# placa_mux.net
KiCad netlist of a schematic drawn in EAGLE
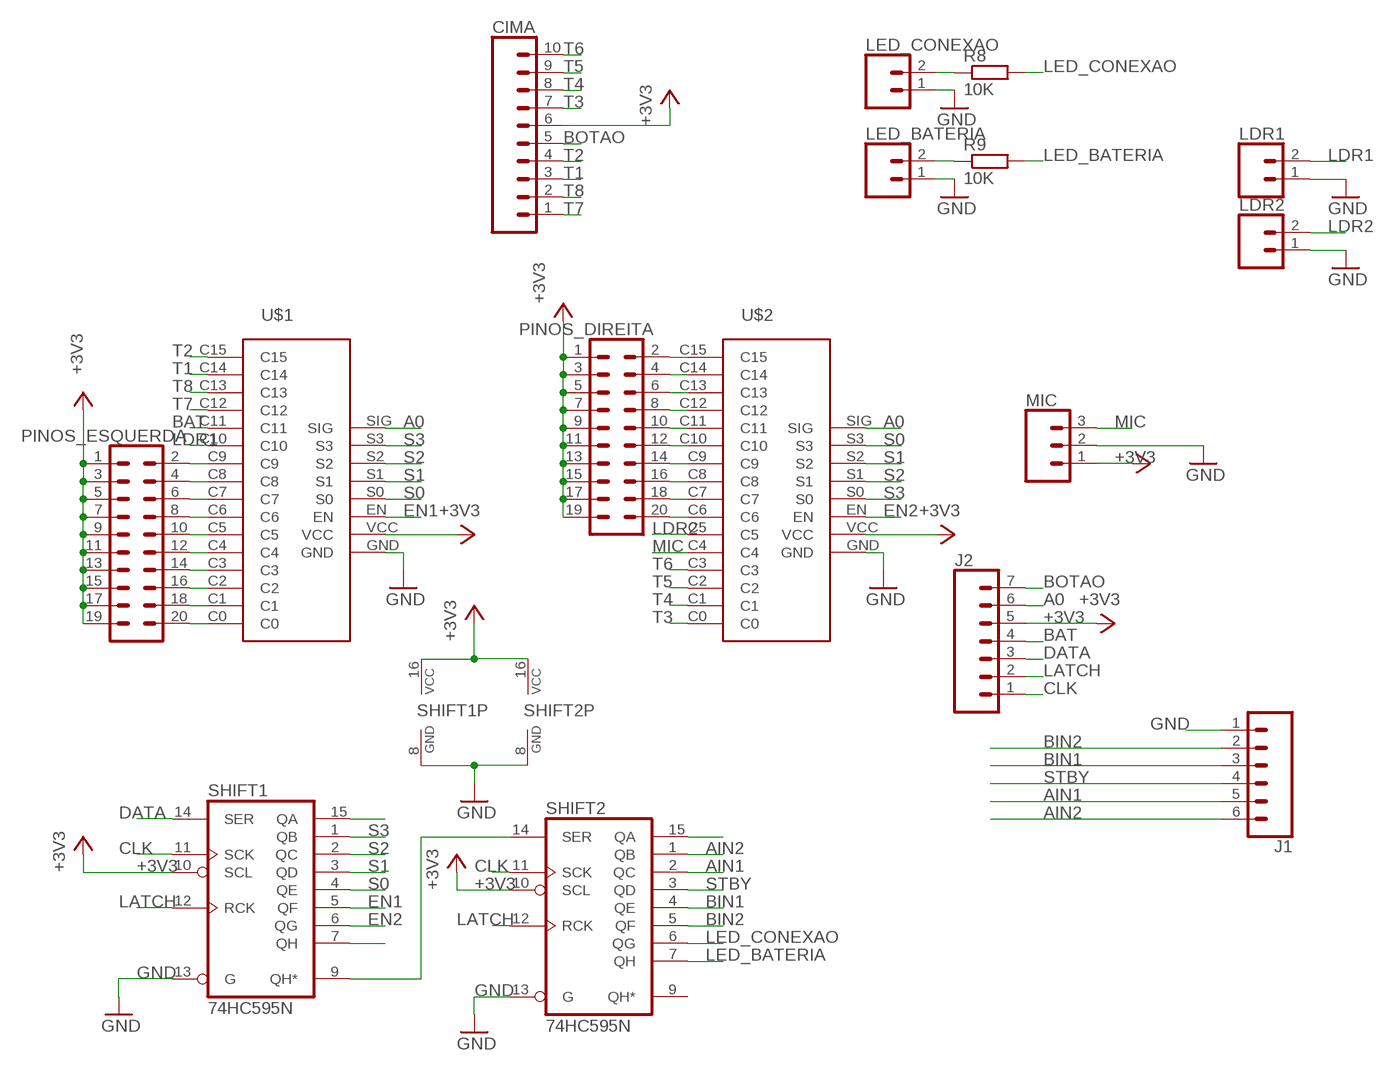
[diagram p0: schematic, sheet 1]

(export (version "E")
  (design (tool "Eeschema 10.0.6"))
  (components
    (comp (ref "CIMA")
      (value "CONN_10\"")
      (footprint "eagle-import:1X10")
      (libsource (lib "eagle-import") (part "CONN_10{dblquote}"))
    )
    (comp (ref "J1")
      (value "CONN_06SILK_FEMALE_PTH")
      (footprint "eagle-import:1X06")
      (libsource (lib "eagle-import") (part "CONN_06SILK_FEMALE_PTH"))
    )
    (comp (ref "J2")
      (value "CONN_07")
      (footprint "eagle-import:1X07")
      (libsource (lib "eagle-import") (part "CONN_07"))
    )
    (comp (ref "LDR1")
      (value "CONN_02")
      (footprint "eagle-import:1X02")
      (libsource (lib "eagle-import") (part "CONN_02"))
    )
    (comp (ref "LDR2")
      (value "CONN_02")
      (footprint "eagle-import:1X02")
      (libsource (lib "eagle-import") (part "CONN_02"))
    )
    (comp (ref "LED_BATERIA")
      (value "CONN_02")
      (footprint "eagle-import:1X02")
      (libsource (lib "eagle-import") (part "CONN_02"))
    )
    (comp (ref "LED_CONEXAO")
      (value "CONN_02")
      (footprint "eagle-import:1X02")
      (libsource (lib "eagle-import") (part "CONN_02"))
    )
    (comp (ref "MIC")
      (value "CONN_03")
      (footprint "eagle-import:1X03")
      (libsource (lib "eagle-import") (part "CONN_03"))
    )
    (comp (ref "PINOS_DIREITA")
      (value "CONN_10X2")
      (footprint "eagle-import:2X10")
      (libsource (lib "eagle-import") (part "CONN_10X2"))
    )
    (comp (ref "PINOS_ESQUERDA")
      (value "CONN_10X2")
      (footprint "eagle-import:2X10")
      (libsource (lib "eagle-import") (part "CONN_10X2"))
    )
    (comp (ref "R8")
      (value "10K")
      (footprint "eagle-import:0204_7")
      (libsource (lib "eagle-import") (part "R-EU_0204/7"))
    )
    (comp (ref "R9")
      (value "10K")
      (footprint "eagle-import:0204_7")
      (libsource (lib "eagle-import") (part "R-EU_0204/7"))
    )
    (comp (ref "SHIFT1")
      (value "74HC595N")
      (footprint "eagle-import:DIL16")
      (libsource (lib "eagle-import") (part "74595NHC"))
    )
    (comp (ref "SHIFT2")
      (value "74HC595N")
      (footprint "eagle-import:DIL16")
      (libsource (lib "eagle-import") (part "74595NHC"))
    )
    (comp (ref "U$1")
      (value "4067_MODULE")
      (footprint "eagle-import:4067_MODULE")
      (libsource (lib "eagle-import") (part "4067_MODULE"))
    )
    (comp (ref "U$2")
      (value "4067_MODULE")
      (footprint "eagle-import:4067_MODULE")
      (libsource (lib "eagle-import") (part "4067_MODULE"))
    )
  )
  (nets
    (net (code "1") (name "+3V3") (class "Default")
      (node (ref "CIMA") (pin "6") (pinfunction "6_6") (pintype "passive"))
      (node (ref "J2") (pin "5") (pinfunction "5_5") (pintype "passive"))
      (node (ref "MIC") (pin "1") (pinfunction "1_1") (pintype "passive"))
      (node (ref "PINOS_DIREITA") (pin "1") (pinfunction "1_1") (pintype "passive"))
      (node (ref "PINOS_DIREITA") (pin "11") (pinfunction "11_11") (pintype "passive"))
      (node (ref "PINOS_DIREITA") (pin "13") (pinfunction "13_13") (pintype "passive"))
      (node (ref "PINOS_DIREITA") (pin "15") (pinfunction "15_15") (pintype "passive"))
      (node (ref "PINOS_DIREITA") (pin "17") (pinfunction "17_17") (pintype "passive"))
      (node (ref "PINOS_DIREITA") (pin "19") (pinfunction "19_19") (pintype "passive"))
      (node (ref "PINOS_DIREITA") (pin "3") (pinfunction "3_3") (pintype "passive"))
      (node (ref "PINOS_DIREITA") (pin "5") (pinfunction "5_5") (pintype "passive"))
      (node (ref "PINOS_DIREITA") (pin "7") (pinfunction "7_7") (pintype "passive"))
      (node (ref "PINOS_DIREITA") (pin "9") (pinfunction "9_9") (pintype "passive"))
      (node (ref "PINOS_ESQUERDA") (pin "1") (pinfunction "1_1") (pintype "passive"))
      (node (ref "PINOS_ESQUERDA") (pin "11") (pinfunction "11_11") (pintype "passive"))
      (node (ref "PINOS_ESQUERDA") (pin "13") (pinfunction "13_13") (pintype "passive"))
      (node (ref "PINOS_ESQUERDA") (pin "15") (pinfunction "15_15") (pintype "passive"))
      (node (ref "PINOS_ESQUERDA") (pin "17") (pinfunction "17_17") (pintype "passive"))
      (node (ref "PINOS_ESQUERDA") (pin "19") (pinfunction "19_19") (pintype "passive"))
      (node (ref "PINOS_ESQUERDA") (pin "3") (pinfunction "3_3") (pintype "passive"))
      (node (ref "PINOS_ESQUERDA") (pin "5") (pinfunction "5_5") (pintype "passive"))
      (node (ref "PINOS_ESQUERDA") (pin "7") (pinfunction "7_7") (pintype "passive"))
      (node (ref "PINOS_ESQUERDA") (pin "9") (pinfunction "9_9") (pintype "passive"))
      (node (ref "SHIFT1") (pin "10") (pinfunction "SCL_10") (pintype "input"))
      (node (ref "SHIFT1") (pin "16") (pinfunction "VCC_16") (pintype "power_in"))
      (node (ref "SHIFT2") (pin "10") (pinfunction "SCL_10") (pintype "input"))
      (node (ref "SHIFT2") (pin "16") (pinfunction "VCC_16") (pintype "power_in"))
      (node (ref "U$1") (pin "VCC") (pinfunction "VCC_VCC") (pintype "power_in"))
      (node (ref "U$2") (pin "VCC") (pinfunction "VCC_VCC") (pintype "power_in"))
    )
    (net (code "2") (name "/A0") (class "Default")
      (node (ref "J2") (pin "6") (pinfunction "6_6") (pintype "passive"))
      (node (ref "U$1") (pin "SIG") (pinfunction "SIG_SIG") (pintype "bidirectional"))
      (node (ref "U$2") (pin "SIG") (pinfunction "SIG_SIG") (pintype "bidirectional"))
    )
    (net (code "3") (name "/AIN1") (class "Default")
      (node (ref "J1") (pin "5") (pinfunction "5_5") (pintype "passive"))
      (node (ref "SHIFT2") (pin "2") (pinfunction "QC_2") (pintype "tri_state"))
    )
    (net (code "4") (name "/AIN2") (class "Default")
      (node (ref "J1") (pin "6") (pinfunction "6_6") (pintype "passive"))
      (node (ref "SHIFT2") (pin "1") (pinfunction "QB_1") (pintype "tri_state"))
    )
    (net (code "5") (name "/BAT") (class "Default")
      (node (ref "J2") (pin "4") (pinfunction "4_4") (pintype "passive"))
      (node (ref "U$1") (pin "C11") (pinfunction "C11_C11") (pintype "bidirectional"))
    )
    (net (code "6") (name "/BIN1") (class "Default")
      (node (ref "J1") (pin "3") (pinfunction "3_3") (pintype "passive"))
      (node (ref "SHIFT2") (pin "4") (pinfunction "QE_4") (pintype "tri_state"))
    )
    (net (code "7") (name "/BIN2") (class "Default")
      (node (ref "J1") (pin "2") (pinfunction "2_2") (pintype "passive"))
      (node (ref "SHIFT2") (pin "5") (pinfunction "QF_5") (pintype "tri_state"))
    )
    (net (code "8") (name "/BOTAO") (class "Default")
      (node (ref "CIMA") (pin "5") (pinfunction "5_5") (pintype "passive"))
      (node (ref "J2") (pin "7") (pinfunction "7_7") (pintype "passive"))
    )
    (net (code "9") (name "/CLK") (class "Default")
      (node (ref "J2") (pin "1") (pinfunction "1_1") (pintype "passive"))
      (node (ref "SHIFT1") (pin "11") (pinfunction "SCK_11") (pintype "input"))
      (node (ref "SHIFT2") (pin "11") (pinfunction "SCK_11") (pintype "input"))
    )
    (net (code "10") (name "/DATA") (class "Default")
      (node (ref "J2") (pin "3") (pinfunction "3_3") (pintype "passive"))
      (node (ref "SHIFT1") (pin "14") (pinfunction "SER_14") (pintype "input"))
    )
    (net (code "11") (name "/EN1") (class "Default")
      (node (ref "SHIFT1") (pin "5") (pinfunction "QF_5") (pintype "tri_state"))
      (node (ref "U$1") (pin "EN") (pinfunction "EN_EN") (pintype "bidirectional"))
    )
    (net (code "12") (name "/EN2") (class "Default")
      (node (ref "SHIFT1") (pin "6") (pinfunction "QG_6") (pintype "tri_state"))
      (node (ref "U$2") (pin "EN") (pinfunction "EN_EN") (pintype "bidirectional"))
    )
    (net (code "13") (name "/LATCH") (class "Default")
      (node (ref "J2") (pin "2") (pinfunction "2_2") (pintype "passive"))
      (node (ref "SHIFT1") (pin "12") (pinfunction "RCK_12") (pintype "input"))
      (node (ref "SHIFT2") (pin "12") (pinfunction "RCK_12") (pintype "input"))
    )
    (net (code "14") (name "/LDR1") (class "Default")
      (node (ref "LDR1") (pin "2") (pinfunction "2_2") (pintype "passive"))
      (node (ref "U$1") (pin "C10") (pinfunction "C10_C10") (pintype "bidirectional"))
    )
    (net (code "15") (name "/LDR2") (class "Default")
      (node (ref "LDR2") (pin "2") (pinfunction "2_2") (pintype "passive"))
      (node (ref "U$2") (pin "C5") (pinfunction "C5_C5") (pintype "bidirectional"))
    )
    (net (code "16") (name "/LED_BATERIA") (class "Default")
      (node (ref "R9") (pin "2") (pinfunction "2_2") (pintype "passive"))
      (node (ref "SHIFT2") (pin "7") (pinfunction "QH_7") (pintype "tri_state"))
    )
    (net (code "17") (name "/LED_CONEXAO") (class "Default")
      (node (ref "R8") (pin "2") (pinfunction "2_2") (pintype "passive"))
      (node (ref "SHIFT2") (pin "6") (pinfunction "QG_6") (pintype "tri_state"))
    )
    (net (code "18") (name "/MIC") (class "Default")
      (node (ref "MIC") (pin "3") (pinfunction "3_3") (pintype "passive"))
      (node (ref "U$2") (pin "C4") (pinfunction "C4_C4") (pintype "bidirectional"))
    )
    (net (code "19") (name "/S0") (class "Default")
      (node (ref "SHIFT1") (pin "4") (pinfunction "QE_4") (pintype "tri_state"))
      (node (ref "U$1") (pin "S0") (pinfunction "S0_S0") (pintype "bidirectional"))
      (node (ref "U$2") (pin "S3") (pinfunction "S3_S3") (pintype "bidirectional"))
    )
    (net (code "20") (name "/S1") (class "Default")
      (node (ref "SHIFT1") (pin "3") (pinfunction "QD_3") (pintype "tri_state"))
      (node (ref "U$1") (pin "S1") (pinfunction "S1_S1") (pintype "bidirectional"))
      (node (ref "U$2") (pin "S2") (pinfunction "S2_S2") (pintype "bidirectional"))
    )
    (net (code "21") (name "/S2") (class "Default")
      (node (ref "SHIFT1") (pin "2") (pinfunction "QC_2") (pintype "tri_state"))
      (node (ref "U$1") (pin "S2") (pinfunction "S2_S2") (pintype "bidirectional"))
      (node (ref "U$2") (pin "S1") (pinfunction "S1_S1") (pintype "bidirectional"))
    )
    (net (code "22") (name "/S3") (class "Default")
      (node (ref "SHIFT1") (pin "1") (pinfunction "QB_1") (pintype "tri_state"))
      (node (ref "U$1") (pin "S3") (pinfunction "S3_S3") (pintype "bidirectional"))
      (node (ref "U$2") (pin "S0") (pinfunction "S0_S0") (pintype "bidirectional"))
    )
    (net (code "23") (name "/STBY") (class "Default")
      (node (ref "J1") (pin "4") (pinfunction "4_4") (pintype "passive"))
      (node (ref "SHIFT2") (pin "3") (pinfunction "QD_3") (pintype "tri_state"))
    )
    (net (code "24") (name "/T1") (class "Default")
      (node (ref "CIMA") (pin "3") (pinfunction "3_3") (pintype "passive"))
      (node (ref "U$1") (pin "C14") (pinfunction "C14_C14") (pintype "bidirectional"))
    )
    (net (code "25") (name "/T2") (class "Default")
      (node (ref "CIMA") (pin "4") (pinfunction "4_4") (pintype "passive"))
      (node (ref "U$1") (pin "C15") (pinfunction "C15_C15") (pintype "bidirectional"))
    )
    (net (code "26") (name "/T3") (class "Default")
      (node (ref "CIMA") (pin "7") (pinfunction "7_7") (pintype "passive"))
      (node (ref "U$2") (pin "C0") (pinfunction "C0_C0") (pintype "bidirectional"))
    )
    (net (code "27") (name "/T4") (class "Default")
      (node (ref "CIMA") (pin "8") (pinfunction "8_8") (pintype "passive"))
      (node (ref "U$2") (pin "C1") (pinfunction "C1_C1") (pintype "bidirectional"))
    )
    (net (code "28") (name "/T5") (class "Default")
      (node (ref "CIMA") (pin "9") (pinfunction "9_9") (pintype "passive"))
      (node (ref "U$2") (pin "C2") (pinfunction "C2_C2") (pintype "bidirectional"))
    )
    (net (code "29") (name "/T6") (class "Default")
      (node (ref "CIMA") (pin "10") (pinfunction "10_10") (pintype "passive"))
      (node (ref "U$2") (pin "C3") (pinfunction "C3_C3") (pintype "bidirectional"))
    )
    (net (code "30") (name "/T7") (class "Default")
      (node (ref "CIMA") (pin "1") (pinfunction "1_1") (pintype "passive"))
      (node (ref "U$1") (pin "C12") (pinfunction "C12_C12") (pintype "bidirectional"))
    )
    (net (code "31") (name "/T8") (class "Default")
      (node (ref "CIMA") (pin "2") (pinfunction "2_2") (pintype "passive"))
      (node (ref "U$1") (pin "C13") (pinfunction "C13_C13") (pintype "bidirectional"))
    )
    (net (code "32") (name "GND") (class "Default")
      (node (ref "J1") (pin "1") (pinfunction "1_1") (pintype "passive"))
      (node (ref "LDR1") (pin "1") (pinfunction "1_1") (pintype "passive"))
      (node (ref "LDR2") (pin "1") (pinfunction "1_1") (pintype "passive"))
      (node (ref "LED_BATERIA") (pin "1") (pinfunction "1_1") (pintype "passive"))
      (node (ref "LED_CONEXAO") (pin "1") (pinfunction "1_1") (pintype "passive"))
      (node (ref "MIC") (pin "2") (pinfunction "2_2") (pintype "passive"))
      (node (ref "SHIFT1") (pin "13") (pinfunction "G_13") (pintype "input"))
      (node (ref "SHIFT1") (pin "8") (pinfunction "GND_8") (pintype "power_in"))
      (node (ref "SHIFT2") (pin "13") (pinfunction "G_13") (pintype "input"))
      (node (ref "SHIFT2") (pin "8") (pinfunction "GND_8") (pintype "power_in"))
      (node (ref "U$1") (pin "GND") (pinfunction "GND_GND") (pintype "bidirectional"))
      (node (ref "U$2") (pin "GND") (pinfunction "GND_GND") (pintype "bidirectional"))
    )
    (net (code "33") (name "Net-(LED_BATERIA-Pad2)") (class "Default")
      (node (ref "LED_BATERIA") (pin "2") (pinfunction "2_2") (pintype "passive"))
      (node (ref "R9") (pin "1") (pinfunction "1_1") (pintype "passive"))
    )
    (net (code "34") (name "Net-(LED_CONEXAO-Pad2)") (class "Default")
      (node (ref "LED_CONEXAO") (pin "2") (pinfunction "2_2") (pintype "passive"))
      (node (ref "R8") (pin "1") (pinfunction "1_1") (pintype "passive"))
    )
    (net (code "35") (name "Net-(PINOS_DIREITA-Pad2)") (class "Default")
      (node (ref "PINOS_DIREITA") (pin "2") (pinfunction "2_2") (pintype "passive"))
      (node (ref "U$2") (pin "C15") (pinfunction "C15_C15") (pintype "bidirectional"))
    )
    (net (code "36") (name "Net-(PINOS_DIREITA-Pad4)") (class "Default")
      (node (ref "PINOS_DIREITA") (pin "4") (pinfunction "4_4") (pintype "passive"))
      (node (ref "U$2") (pin "C14") (pinfunction "C14_C14") (pintype "bidirectional"))
    )
    (net (code "37") (name "Net-(PINOS_DIREITA-Pad6)") (class "Default")
      (node (ref "PINOS_DIREITA") (pin "6") (pinfunction "6_6") (pintype "passive"))
      (node (ref "U$2") (pin "C13") (pinfunction "C13_C13") (pintype "bidirectional"))
    )
    (net (code "38") (name "Net-(PINOS_DIREITA-Pad8)") (class "Default")
      (node (ref "PINOS_DIREITA") (pin "8") (pinfunction "8_8") (pintype "passive"))
      (node (ref "U$2") (pin "C12") (pinfunction "C12_C12") (pintype "bidirectional"))
    )
    (net (code "39") (name "Net-(PINOS_DIREITA-Pad10)") (class "Default")
      (node (ref "PINOS_DIREITA") (pin "10") (pinfunction "10_10") (pintype "passive"))
      (node (ref "U$2") (pin "C11") (pinfunction "C11_C11") (pintype "bidirectional"))
    )
    (net (code "40") (name "Net-(PINOS_DIREITA-Pad12)") (class "Default")
      (node (ref "PINOS_DIREITA") (pin "12") (pinfunction "12_12") (pintype "passive"))
      (node (ref "U$2") (pin "C10") (pinfunction "C10_C10") (pintype "bidirectional"))
    )
    (net (code "41") (name "Net-(PINOS_DIREITA-Pad14)") (class "Default")
      (node (ref "PINOS_DIREITA") (pin "14") (pinfunction "14_14") (pintype "passive"))
      (node (ref "U$2") (pin "C9") (pinfunction "C9_C9") (pintype "bidirectional"))
    )
    (net (code "42") (name "Net-(PINOS_DIREITA-Pad16)") (class "Default")
      (node (ref "PINOS_DIREITA") (pin "16") (pinfunction "16_16") (pintype "passive"))
      (node (ref "U$2") (pin "C8") (pinfunction "C8_C8") (pintype "bidirectional"))
    )
    (net (code "43") (name "Net-(PINOS_DIREITA-Pad18)") (class "Default")
      (node (ref "PINOS_DIREITA") (pin "18") (pinfunction "18_18") (pintype "passive"))
      (node (ref "U$2") (pin "C7") (pinfunction "C7_C7") (pintype "bidirectional"))
    )
    (net (code "44") (name "Net-(PINOS_DIREITA-Pad20)") (class "Default")
      (node (ref "PINOS_DIREITA") (pin "20") (pinfunction "20_20") (pintype "passive"))
      (node (ref "U$2") (pin "C6") (pinfunction "C6_C6") (pintype "bidirectional"))
    )
    (net (code "45") (name "Net-(PINOS_ESQUERDA-Pad2)") (class "Default")
      (node (ref "PINOS_ESQUERDA") (pin "2") (pinfunction "2_2") (pintype "passive"))
      (node (ref "U$1") (pin "C9") (pinfunction "C9_C9") (pintype "bidirectional"))
    )
    (net (code "46") (name "Net-(PINOS_ESQUERDA-Pad4)") (class "Default")
      (node (ref "PINOS_ESQUERDA") (pin "4") (pinfunction "4_4") (pintype "passive"))
      (node (ref "U$1") (pin "C8") (pinfunction "C8_C8") (pintype "bidirectional"))
    )
    (net (code "47") (name "Net-(PINOS_ESQUERDA-Pad6)") (class "Default")
      (node (ref "PINOS_ESQUERDA") (pin "6") (pinfunction "6_6") (pintype "passive"))
      (node (ref "U$1") (pin "C7") (pinfunction "C7_C7") (pintype "bidirectional"))
    )
    (net (code "48") (name "Net-(PINOS_ESQUERDA-Pad8)") (class "Default")
      (node (ref "PINOS_ESQUERDA") (pin "8") (pinfunction "8_8") (pintype "passive"))
      (node (ref "U$1") (pin "C6") (pinfunction "C6_C6") (pintype "bidirectional"))
    )
    (net (code "49") (name "Net-(PINOS_ESQUERDA-Pad10)") (class "Default")
      (node (ref "PINOS_ESQUERDA") (pin "10") (pinfunction "10_10") (pintype "passive"))
      (node (ref "U$1") (pin "C5") (pinfunction "C5_C5") (pintype "bidirectional"))
    )
    (net (code "50") (name "Net-(PINOS_ESQUERDA-Pad12)") (class "Default")
      (node (ref "PINOS_ESQUERDA") (pin "12") (pinfunction "12_12") (pintype "passive"))
      (node (ref "U$1") (pin "C4") (pinfunction "C4_C4") (pintype "bidirectional"))
    )
    (net (code "51") (name "Net-(PINOS_ESQUERDA-Pad14)") (class "Default")
      (node (ref "PINOS_ESQUERDA") (pin "14") (pinfunction "14_14") (pintype "passive"))
      (node (ref "U$1") (pin "C3") (pinfunction "C3_C3") (pintype "bidirectional"))
    )
    (net (code "52") (name "Net-(PINOS_ESQUERDA-Pad16)") (class "Default")
      (node (ref "PINOS_ESQUERDA") (pin "16") (pinfunction "16_16") (pintype "passive"))
      (node (ref "U$1") (pin "C2") (pinfunction "C2_C2") (pintype "bidirectional"))
    )
    (net (code "53") (name "Net-(PINOS_ESQUERDA-Pad18)") (class "Default")
      (node (ref "PINOS_ESQUERDA") (pin "18") (pinfunction "18_18") (pintype "passive"))
      (node (ref "U$1") (pin "C1") (pinfunction "C1_C1") (pintype "bidirectional"))
    )
    (net (code "54") (name "Net-(PINOS_ESQUERDA-Pad20)") (class "Default")
      (node (ref "PINOS_ESQUERDA") (pin "20") (pinfunction "20_20") (pintype "passive"))
      (node (ref "U$1") (pin "C0") (pinfunction "C0_C0") (pintype "bidirectional"))
    )
    (net (code "55") (name "Net-(SHIFT1A-QH*)") (class "Default")
      (node (ref "SHIFT1") (pin "9") (pinfunction "QH*_9") (pintype "tri_state"))
      (node (ref "SHIFT2") (pin "14") (pinfunction "SER_14") (pintype "input"))
    )
    (net (code "56") (name "unconnected-(SHIFT1A-QA-Pad15)") (class "Default")
      (node (ref "SHIFT1") (pin "15") (pinfunction "QA_15") (pintype "tri_state"))
    )
    (net (code "57") (name "unconnected-(SHIFT1A-QH-Pad7)") (class "Default")
      (node (ref "SHIFT1") (pin "7") (pinfunction "QH_7") (pintype "tri_state"))
    )
    (net (code "58") (name "unconnected-(SHIFT2A-QA-Pad15)") (class "Default")
      (node (ref "SHIFT2") (pin "15") (pinfunction "QA_15") (pintype "tri_state"))
    )
    (net (code "59") (name "unconnected-(SHIFT2A-QH*-Pad9)") (class "Default")
      (node (ref "SHIFT2") (pin "9") (pinfunction "QH*_9") (pintype "tri_state"))
    )
  )
)
